# wqm.net
KiCad netlist of a schematic drawn in EAGLE
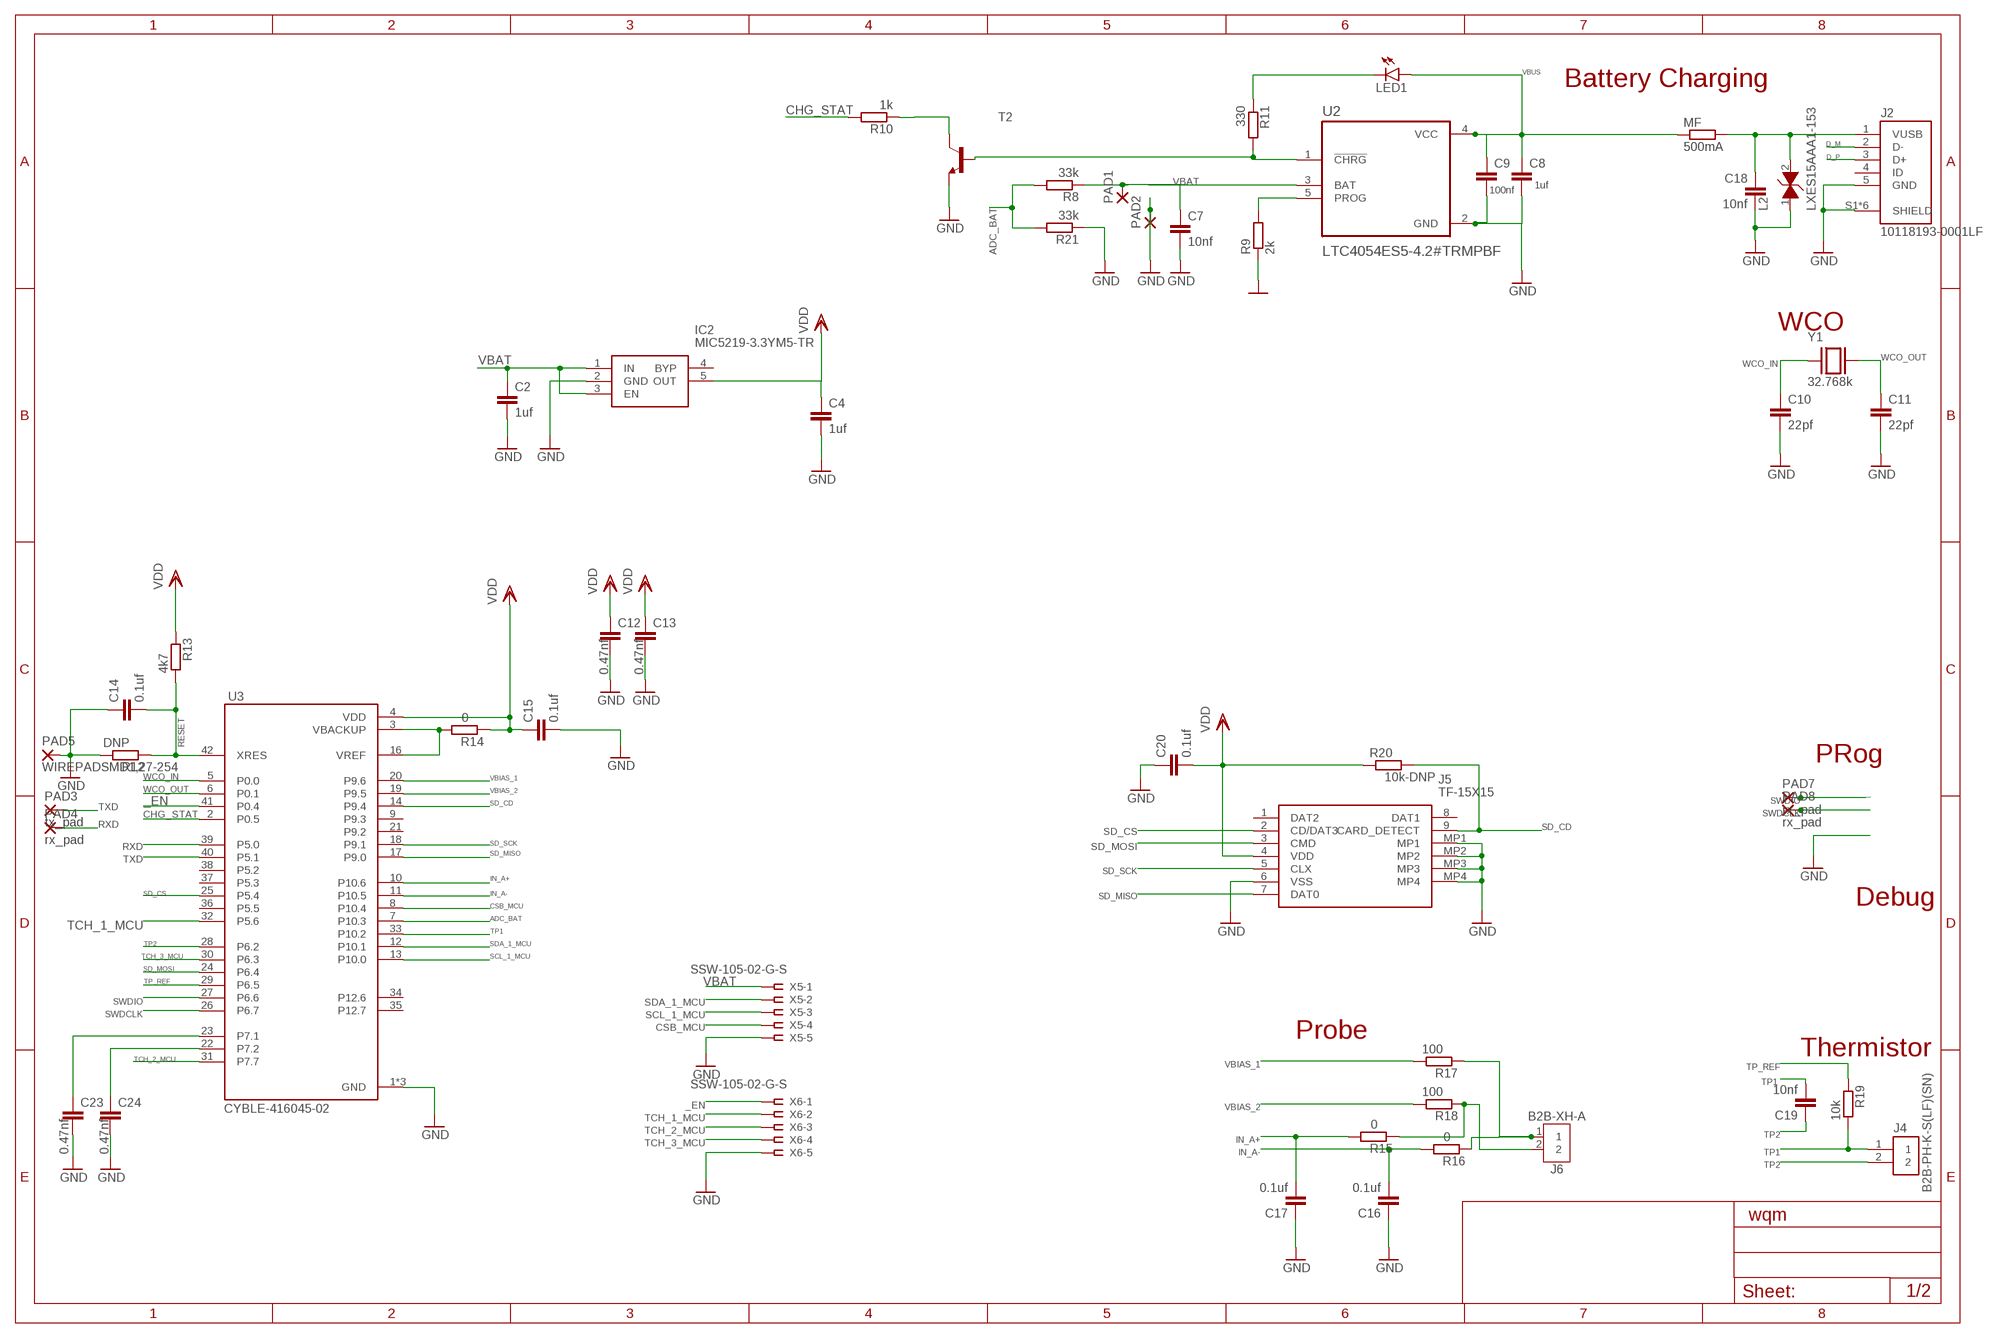
[diagram p0: schematic, sheet 1]
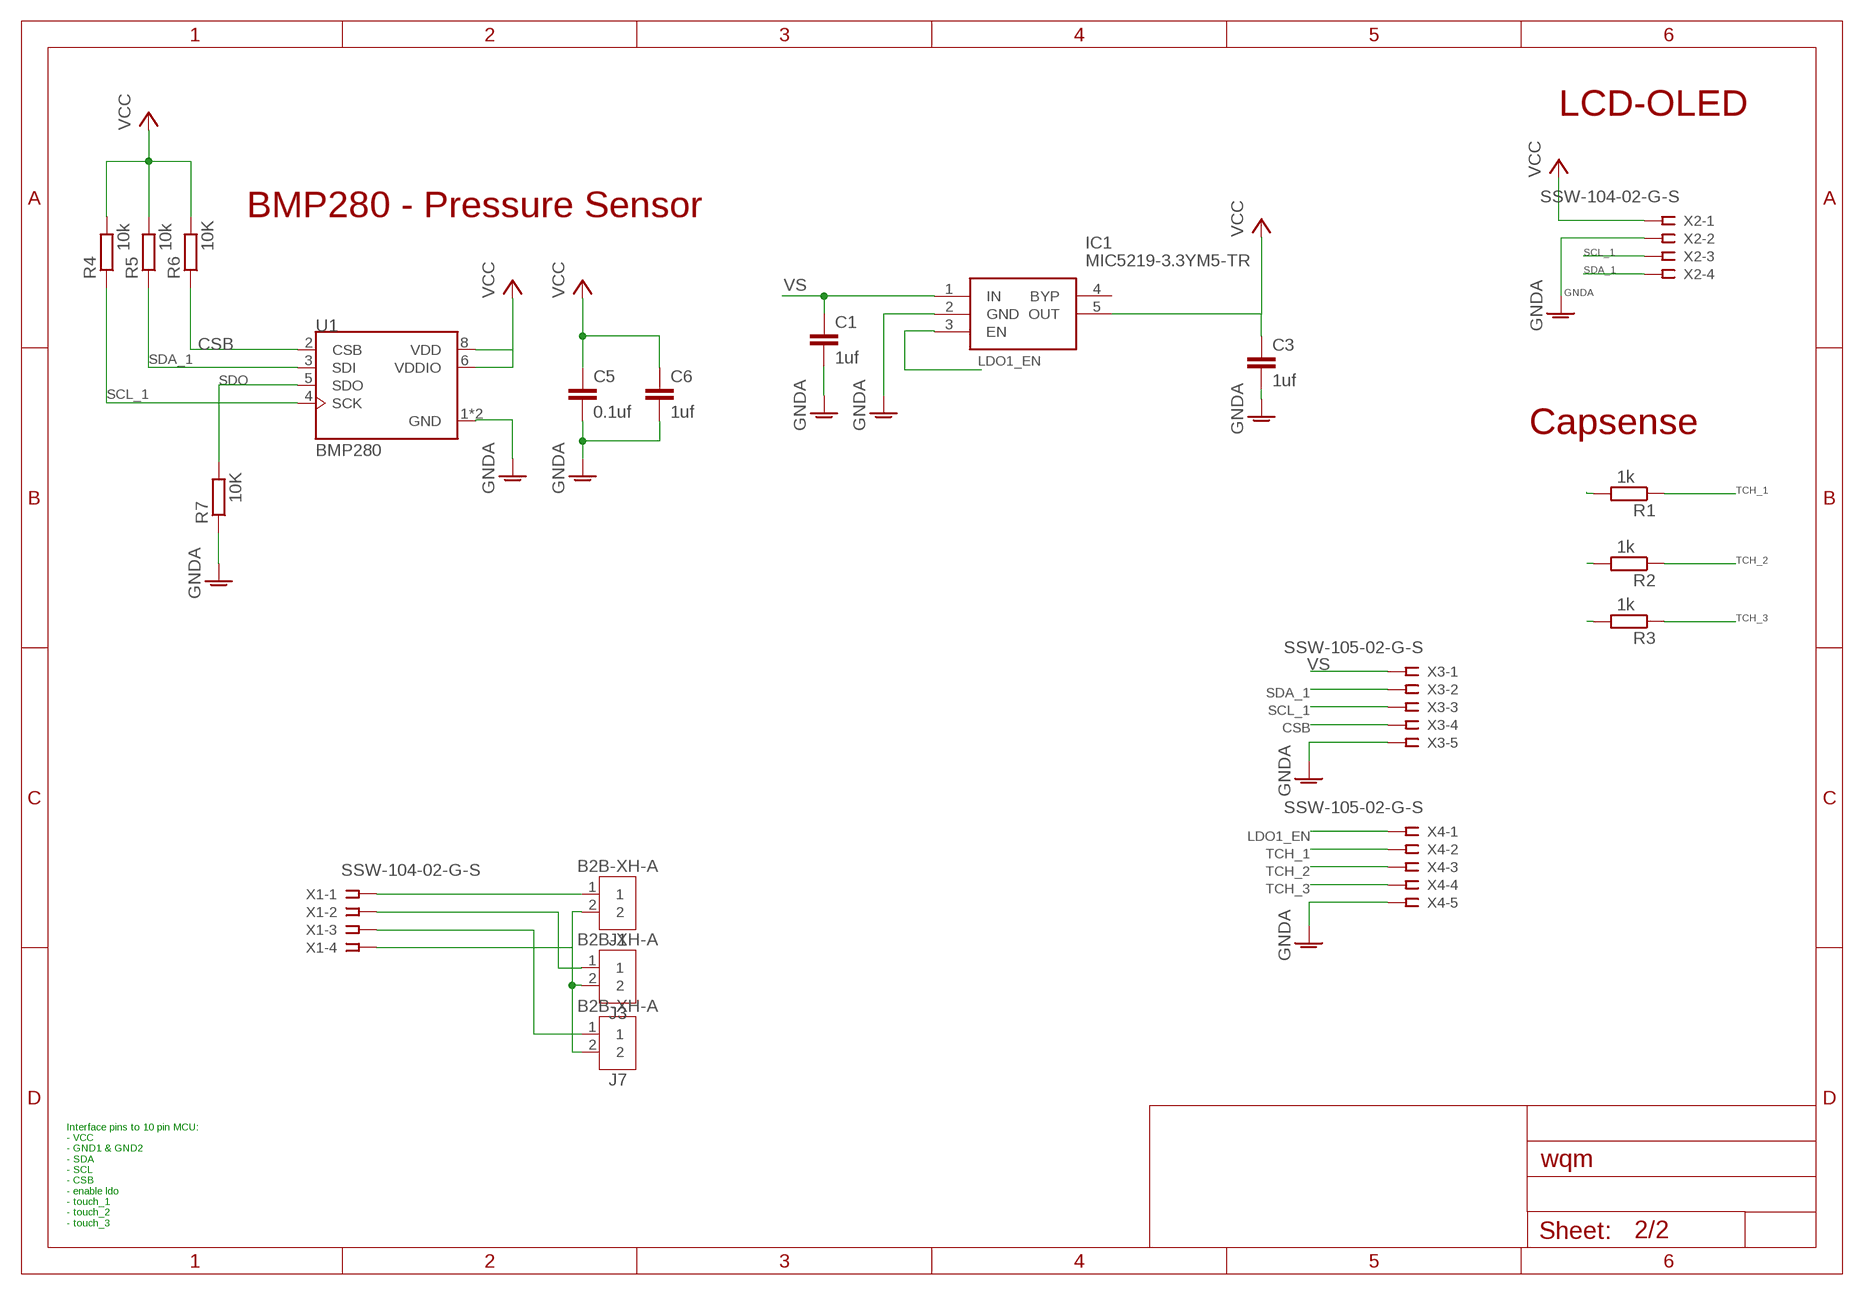
[diagram p1: schematic, sheet 2]

(export (version "E")
  (design (tool "Eeschema 10.0.6"))
  (components
    (comp (ref "C2")
      (value "1uf")
      (footprint "eagle-import:C0603K")
      (libsource (lib "eagle-import") (part "C-EUC0603K"))
    )
    (comp (ref "C4")
      (value "1uf")
      (footprint "eagle-import:C0603K")
      (libsource (lib "eagle-import") (part "C-EUC0603K"))
    )
    (comp (ref "C7")
      (value "10nf")
      (footprint "eagle-import:C0603K")
      (libsource (lib "eagle-import") (part "C-EUC0603K"))
    )
    (comp (ref "C8")
      (value "1uf")
      (footprint "eagle-import:C0603K")
      (libsource (lib "eagle-import") (part "C-EUC0603K"))
    )
    (comp (ref "C9")
      (value "100nf")
      (footprint "eagle-import:C0603K")
      (libsource (lib "eagle-import") (part "C-EUC0603K"))
    )
    (comp (ref "C10")
      (value "22pf")
      (footprint "eagle-import:C0402K")
      (libsource (lib "eagle-import") (part "C-EUC0402K"))
    )
    (comp (ref "C11")
      (value "22pf")
      (footprint "eagle-import:C0402K")
      (libsource (lib "eagle-import") (part "C-EUC0402K"))
    )
    (comp (ref "C12")
      (value "0.47nf")
      (footprint "eagle-import:C0402K")
      (libsource (lib "eagle-import") (part "C-EUC0402K"))
    )
    (comp (ref "C13")
      (value "0.47nf")
      (footprint "eagle-import:C0402K")
      (libsource (lib "eagle-import") (part "C-EUC0402K"))
    )
    (comp (ref "C14")
      (value "0.1uf")
      (footprint "eagle-import:C0402K")
      (libsource (lib "eagle-import") (part "C-EUC0402K"))
    )
    (comp (ref "C15")
      (value "0.1uf")
      (footprint "eagle-import:C0603K")
      (libsource (lib "eagle-import") (part "C-EUC0603K"))
    )
    (comp (ref "C16")
      (value "0.1uf")
      (footprint "eagle-import:C0603K")
      (libsource (lib "eagle-import") (part "C-EUC0603K"))
    )
    (comp (ref "C17")
      (value "0.1uf")
      (footprint "eagle-import:C0603K")
      (libsource (lib "eagle-import") (part "C-EUC0603K"))
    )
    (comp (ref "C18")
      (value "10nf")
      (footprint "eagle-import:C0402K")
      (libsource (lib "eagle-import") (part "C-EUC0402K"))
    )
    (comp (ref "C19")
      (value "10nf")
      (footprint "eagle-import:C0402K")
      (libsource (lib "eagle-import") (part "C-EUC0402K"))
    )
    (comp (ref "C20")
      (value "0.1uf")
      (footprint "eagle-import:C0603K")
      (libsource (lib "eagle-import") (part "C-EUC0603K"))
    )
    (comp (ref "C23")
      (value "0.47nf")
      (footprint "eagle-import:C0402K")
      (libsource (lib "eagle-import") (part "C-EUC0402K"))
    )
    (comp (ref "C24")
      (value "0.47nf")
      (footprint "eagle-import:C0402K")
      (libsource (lib "eagle-import") (part "C-EUC0402K"))
    )
    (comp (ref "IC2")
      (value "MIC5219-3.3YM5-TR")
      (footprint "eagle-import:SOT95P280X145-5N")
      (fields (field (name "MOUSER_PART_NUMBER") "998-MIC5219-3.3YM5TR"))
      (libsource (lib "eagle-import") (part "MIC5219-3.3YM5-TR"))
    )
    (comp (ref "J2")
      (value "10118193-0001LF")
      (footprint "eagle-import:AMPHENOL_10118193-0001LF")
      (fields (field (name "MF") "Amphenol"))
      (libsource (lib "eagle-import") (part "10118193-0001LF"))
    )
    (comp (ref "J4")
      (value "B2B-PH-K-S(LF)(SN)")
      (footprint "eagle-import:JST_B2B-PH-K-S(LF)(SN)")
      (fields (field (name "MF") "JST Sales"))
      (libsource (lib "eagle-import") (part "B2B-PH-K-S(LF)(SN)"))
    )
    (comp (ref "J5")
      (value "TF-15X15")
      (footprint "eagle-import:TF15X15")
      (libsource (lib "eagle-import") (part "TF-15X15"))
    )
    (comp (ref "J6")
      (value "B2B-XH-A")
      (footprint "eagle-import:B2B-XH-A")
      (fields (field (name "MF") "JST Sales"))
      (libsource (lib "eagle-import") (part "B2B-XH-A"))
    )
    (comp (ref "L2")
      (value "LXES15AAA1-153")
      (footprint "eagle-import:INDC1005X45")
      (fields (field (name "MF") "Murata"))
      (libsource (lib "eagle-import") (part "LXES15AAA1-153"))
    )
    (comp (ref "LED1")
      (value "LEDSML0603")
      (footprint "eagle-import:SML0603")
      (libsource (lib "eagle-import") (part "LEDSML0603"))
    )
    (comp (ref "MF")
      (value "500mA")
      (footprint "eagle-import:R0805")
      (libsource (lib "eagle-import") (part "R-EU_R0805"))
    )
    (comp (ref "PAD1")
      (value "SMD2")
      (footprint "eagle-import:SMD1,27-2,54")
      (libsource (lib "eagle-import") (part "SMD2"))
    )
    (comp (ref "PAD2")
      (value "SMD2")
      (footprint "eagle-import:SMD1,27-2,54")
      (libsource (lib "eagle-import") (part "SMD2"))
    )
    (comp (ref "PAD3")
      (value "tx_pad")
      (footprint "eagle-import:SMD1,27-2,54")
      (libsource (lib "eagle-import") (part "WIREPADSMD1,27-254"))
    )
    (comp (ref "PAD4")
      (value "rx_pad")
      (footprint "eagle-import:SMD1,27-2,54")
      (libsource (lib "eagle-import") (part "WIREPADSMD1,27-254"))
    )
    (comp (ref "PAD5")
      (value "WIREPADSMD1,27-254")
      (footprint "eagle-import:SMD1,27-2,54")
      (libsource (lib "eagle-import") (part "WIREPADSMD1,27-254"))
    )
    (comp (ref "PAD7")
      (value "rx_pad")
      (footprint "eagle-import:SMD1,27-2,54")
      (libsource (lib "eagle-import") (part "WIREPADSMD1,27-254"))
    )
    (comp (ref "PAD8")
      (value "rx_pad")
      (footprint "eagle-import:SMD1,27-2,54")
      (libsource (lib "eagle-import") (part "WIREPADSMD1,27-254"))
    )
    (comp (ref "R8")
      (value "33k")
      (footprint "eagle-import:R0603")
      (libsource (lib "eagle-import") (part "R-EU_R0603"))
    )
    (comp (ref "R9")
      (value "2k")
      (footprint "eagle-import:R0603")
      (libsource (lib "eagle-import") (part "R-EU_R0603"))
    )
    (comp (ref "R10")
      (value "1k")
      (footprint "eagle-import:R0603")
      (libsource (lib "eagle-import") (part "R-EU_R0603"))
    )
    (comp (ref "R11")
      (value "330")
      (footprint "eagle-import:R0603")
      (libsource (lib "eagle-import") (part "R-EU_R0603"))
    )
    (comp (ref "R12")
      (value "DNP")
      (footprint "eagle-import:R0603")
      (libsource (lib "eagle-import") (part "R-EU_R0603"))
    )
    (comp (ref "R13")
      (value "4k7")
      (footprint "eagle-import:R0603")
      (libsource (lib "eagle-import") (part "R-EU_R0603"))
    )
    (comp (ref "R14")
      (value "0")
      (footprint "eagle-import:R0603")
      (libsource (lib "eagle-import") (part "R-EU_R0603"))
    )
    (comp (ref "R15")
      (value "0")
      (footprint "eagle-import:R0603")
      (libsource (lib "eagle-import") (part "R-EU_R0603"))
    )
    (comp (ref "R16")
      (value "0")
      (footprint "eagle-import:R0603")
      (libsource (lib "eagle-import") (part "R-EU_R0603"))
    )
    (comp (ref "R17")
      (value "100")
      (footprint "eagle-import:R0603")
      (libsource (lib "eagle-import") (part "R-EU_R0603"))
    )
    (comp (ref "R18")
      (value "100")
      (footprint "eagle-import:R0603")
      (libsource (lib "eagle-import") (part "R-EU_R0603"))
    )
    (comp (ref "R19")
      (value "10k")
      (footprint "eagle-import:R0603")
      (libsource (lib "eagle-import") (part "R-EU_R0603"))
    )
    (comp (ref "R20")
      (value "10k-DNP")
      (footprint "eagle-import:R0603")
      (libsource (lib "eagle-import") (part "R-EU_R0603"))
    )
    (comp (ref "R21")
      (value "33k")
      (footprint "eagle-import:R0603")
      (libsource (lib "eagle-import") (part "R-EU_R0603"))
    )
    (comp (ref "T2")
      (value "MMBT4401LT1-NPN-SOT23-BEC")
      (footprint "eagle-import:SOT23-BEC")
      (libsource (lib "eagle-import") (part "-NPN-SOT23-BECMMBT4401LT1"))
    )
    (comp (ref "U2")
      (value "LTC4054ES5-4.2#TRMPBF")
      (footprint "eagle-import:SOT95P280X100-5N")
      (fields (field (name "MF") "Analog Devices"))
      (libsource (lib "eagle-import") (part "LTC4054ES5-4.2#TRMPBF"))
    )
    (comp (ref "U3")
      (value "CYBLE-416045-02")
      (footprint "eagle-import:XCVR_CYBLE-416045-02")
      (fields (field (name "MF") "Cypress Semiconductor"))
      (libsource (lib "eagle-import") (part "CYBLE-416045-02"))
    )
    (comp (ref "X5")
      (value "SSW-105-02-G-S")
      (footprint "eagle-import:SSW-105-02-G-S")
      (fields (field (name "MF") "Samtec Inc."))
      (libsource (lib "eagle-import") (part "SSW-105-02-G-S"))
    )
    (comp (ref "X6")
      (value "SSW-105-02-G-S")
      (footprint "eagle-import:SSW-105-02-G-S")
      (fields (field (name "MF") "Samtec Inc."))
      (libsource (lib "eagle-import") (part "SSW-105-02-G-S"))
    )
    (comp (ref "Y1")
      (value "32.768k")
      (footprint "eagle-import:XTAL_MS3V-T1R")
      (fields (field (name "MF") "Micro Crystal") (field (name "MP") "MS3V-T1R"))
      (libsource (lib "eagle-import") (part "MS3V-T1R"))
    )
    (comp (ref "C1")
      (value "1uf")
      (footprint "eagle-import:C0603K")
      (libsource (lib "eagle-import") (part "C-EUC0603K"))
    )
    (comp (ref "C3")
      (value "1uf")
      (footprint "eagle-import:C0603K")
      (libsource (lib "eagle-import") (part "C-EUC0603K"))
    )
    (comp (ref "C5")
      (value "0.1uf")
      (footprint "eagle-import:C0603K")
      (libsource (lib "eagle-import") (part "C-EUC0603K"))
    )
    (comp (ref "C6")
      (value "1uf")
      (footprint "eagle-import:C0603K")
      (libsource (lib "eagle-import") (part "C-EUC0603K"))
    )
    (comp (ref "IC1")
      (value "MIC5219-3.3YM5-TR")
      (footprint "eagle-import:SOT95P280X145-5N")
      (fields (field (name "MOUSER_PART_NUMBER") "998-MIC5219-3.3YM5TR"))
      (libsource (lib "eagle-import") (part "MIC5219-3.3YM5-TR"))
    )
    (comp (ref "J1")
      (value "B2B-XH-A")
      (footprint "eagle-import:B2B-XH-A")
      (fields (field (name "MF") "JST Sales"))
      (libsource (lib "eagle-import") (part "B2B-XH-A"))
    )
    (comp (ref "J3")
      (value "B2B-XH-A")
      (footprint "eagle-import:B2B-XH-A")
      (fields (field (name "MF") "JST Sales"))
      (libsource (lib "eagle-import") (part "B2B-XH-A"))
    )
    (comp (ref "J7")
      (value "B2B-XH-A")
      (footprint "eagle-import:B2B-XH-A")
      (fields (field (name "MF") "JST Sales"))
      (libsource (lib "eagle-import") (part "B2B-XH-A"))
    )
    (comp (ref "R1")
      (value "1k")
      (footprint "eagle-import:R0603")
      (libsource (lib "eagle-import") (part "R-EU_R0603"))
    )
    (comp (ref "R2")
      (value "1k")
      (footprint "eagle-import:R0603")
      (libsource (lib "eagle-import") (part "R-EU_R0603"))
    )
    (comp (ref "R3")
      (value "1k")
      (footprint "eagle-import:R0603")
      (libsource (lib "eagle-import") (part "R-EU_R0603"))
    )
    (comp (ref "R4")
      (value "10k")
      (footprint "eagle-import:R0603")
      (libsource (lib "eagle-import") (part "R-EU_R0603"))
    )
    (comp (ref "R5")
      (value "10k")
      (footprint "eagle-import:R0603")
      (libsource (lib "eagle-import") (part "R-EU_R0603"))
    )
    (comp (ref "R6")
      (value "10K")
      (footprint "eagle-import:R0603")
      (libsource (lib "eagle-import") (part "R-EU_R0603"))
    )
    (comp (ref "R7")
      (value "10K")
      (footprint "eagle-import:R0603")
      (libsource (lib "eagle-import") (part "R-EU_R0603"))
    )
    (comp (ref "U1")
      (value "BMP280")
      (footprint "eagle-import:XDCR_BMP280")
      (fields (field (name "MF") "Bosch"))
      (libsource (lib "eagle-import") (part "BMP280"))
    )
    (comp (ref "X1")
      (value "SSW-104-02-G-S")
      (footprint "eagle-import:SSW-104-02-G-S")
      (fields (field (name "MF") "Samtec Inc."))
      (libsource (lib "eagle-import") (part "SSW-104-02-G-S"))
    )
    (comp (ref "X2")
      (value "SSW-104-02-G-S")
      (footprint "eagle-import:SSW-104-02-G-S")
      (fields (field (name "MF") "Samtec Inc."))
      (libsource (lib "eagle-import") (part "SSW-104-02-G-S"))
    )
    (comp (ref "X3")
      (value "SSW-105-02-G-S")
      (footprint "eagle-import:SSW-105-02-G-S")
      (fields (field (name "MF") "Samtec Inc."))
      (libsource (lib "eagle-import") (part "SSW-105-02-G-S"))
    )
    (comp (ref "X4")
      (value "SSW-105-02-G-S")
      (footprint "eagle-import:SSW-105-02-G-S")
      (fields (field (name "MF") "Samtec Inc."))
      (libsource (lib "eagle-import") (part "SSW-105-02-G-S"))
    )
  )
  (nets
    (net (code "1") (name "ADC_BAT") (class "Default")
      (node (ref "R21") (pin "2") (pinfunction "2_2") (pintype "passive"))
      (node (ref "R8") (pin "2") (pinfunction "2_2") (pintype "passive"))
      (node (ref "U3") (pin "7") (pinfunction "P10.3_7") (pintype "bidirectional"))
    )
    (net (code "2") (name "CHG_STAT") (class "Default")
      (node (ref "R10") (pin "2") (pinfunction "2_2") (pintype "passive"))
      (node (ref "U3") (pin "2") (pinfunction "P0.5_2") (pintype "bidirectional"))
    )
    (net (code "3") (name "CSB") (class "Default")
      (node (ref "R6") (pin "1") (pinfunction "1_1") (pintype "passive"))
      (node (ref "U1") (pin "2") (pinfunction "CSB_2") (pintype "input"))
      (node (ref "X3") (pin "4") (pinfunction "1_4") (pintype "passive"))
    )
    (net (code "4") (name "CSB_MCU") (class "Default")
      (node (ref "U3") (pin "8") (pinfunction "P10.4_8") (pintype "bidirectional"))
      (node (ref "X5") (pin "4") (pinfunction "1_4") (pintype "passive"))
    )
    (net (code "5") (name "D_M") (class "Default")
      (node (ref "J2") (pin "2") (pinfunction "D-_2") (pintype "passive"))
    )
    (net (code "6") (name "D_P") (class "Default")
      (node (ref "J2") (pin "3") (pinfunction "D+_3") (pintype "passive"))
    )
    (net (code "7") (name "GND") (class "Default")
      (node (ref "C10") (pin "2") (pinfunction "2_2") (pintype "passive"))
      (node (ref "C11") (pin "2") (pinfunction "2_2") (pintype "passive"))
      (node (ref "C12") (pin "2") (pinfunction "2_2") (pintype "passive"))
      (node (ref "C13") (pin "2") (pinfunction "2_2") (pintype "passive"))
      (node (ref "C14") (pin "1") (pinfunction "1_1") (pintype "passive"))
      (node (ref "C15") (pin "2") (pinfunction "2_2") (pintype "passive"))
      (node (ref "C16") (pin "1") (pinfunction "1_1") (pintype "passive"))
      (node (ref "C17") (pin "1") (pinfunction "1_1") (pintype "passive"))
      (node (ref "C18") (pin "2") (pinfunction "2_2") (pintype "passive"))
      (node (ref "C2") (pin "2") (pinfunction "2_2") (pintype "passive"))
      (node (ref "C20") (pin "1") (pinfunction "1_1") (pintype "passive"))
      (node (ref "C23") (pin "2") (pinfunction "2_2") (pintype "passive"))
      (node (ref "C24") (pin "2") (pinfunction "2_2") (pintype "passive"))
      (node (ref "C4") (pin "2") (pinfunction "2_2") (pintype "passive"))
      (node (ref "C7") (pin "2") (pinfunction "2_2") (pintype "passive"))
      (node (ref "C8") (pin "2") (pinfunction "2_2") (pintype "passive"))
      (node (ref "C9") (pin "2") (pinfunction "2_2") (pintype "passive"))
      (node (ref "IC2") (pin "2") (pinfunction "GND_2") (pintype "bidirectional"))
      (node (ref "J2") (pin "5") (pinfunction "GND_5") (pintype "passive"))
      (node (ref "J2") (pin "S1") (pinfunction "SHIELD_S1") (pintype "passive"))
      (node (ref "J2") (pin "S2") (pinfunction "SHIELD_S2") (pintype "passive"))
      (node (ref "J2") (pin "S3") (pinfunction "SHIELD_S3") (pintype "passive"))
      (node (ref "J2") (pin "S4") (pinfunction "SHIELD_S4") (pintype "passive"))
      (node (ref "J2") (pin "S5") (pinfunction "SHIELD_S5") (pintype "passive"))
      (node (ref "J2") (pin "S6") (pinfunction "SHIELD_S6") (pintype "passive"))
      (node (ref "J5") (pin "6") (pinfunction "VSS_6") (pintype "bidirectional"))
      (node (ref "J5") (pin "MP1") (pinfunction "MP1_MP1") (pintype "bidirectional"))
      (node (ref "J5") (pin "MP2") (pinfunction "MP2_MP2") (pintype "bidirectional"))
      (node (ref "J5") (pin "MP3") (pinfunction "MP3_MP3") (pintype "bidirectional"))
      (node (ref "J5") (pin "MP4") (pinfunction "MP4_MP4") (pintype "bidirectional"))
      (node (ref "L2") (pin "1") (pinfunction "1_1") (pintype "passive"))
      (node (ref "PAD2") (pin "1") (pinfunction "P_1") (pintype "passive"))
      (node (ref "PAD5") (pin "1") (pinfunction "P_1") (pintype "passive"))
      (node (ref "R12") (pin "2") (pinfunction "2_2") (pintype "passive"))
      (node (ref "R21") (pin "1") (pinfunction "1_1") (pintype "passive"))
      (node (ref "R9") (pin "1") (pinfunction "1_1") (pintype "passive"))
      (node (ref "T2") (pin "E") (pinfunction "E_E") (pintype "passive"))
      (node (ref "U2") (pin "2") (pinfunction "GND_2") (pintype "power_in"))
      (node (ref "U3") (pin "1") (pinfunction "GND_1") (pintype "power_in"))
      (node (ref "U3") (pin "15") (pinfunction "GND_15") (pintype "power_in"))
      (node (ref "U3") (pin "43") (pinfunction "GND_43") (pintype "power_in"))
      (node (ref "X5") (pin "5") (pinfunction "1_5") (pintype "passive"))
      (node (ref "X6") (pin "5") (pinfunction "1_5") (pintype "passive"))
    )
    (net (code "8") (name "GNDA") (class "Default")
      (node (ref "C1") (pin "2") (pinfunction "2_2") (pintype "passive"))
      (node (ref "C3") (pin "2") (pinfunction "2_2") (pintype "passive"))
      (node (ref "C5") (pin "2") (pinfunction "2_2") (pintype "passive"))
      (node (ref "C6") (pin "2") (pinfunction "2_2") (pintype "passive"))
      (node (ref "IC1") (pin "2") (pinfunction "GND_2") (pintype "bidirectional"))
      (node (ref "R7") (pin "1") (pinfunction "1_1") (pintype "passive"))
      (node (ref "U1") (pin "1") (pinfunction "GND_1") (pintype "power_in"))
      (node (ref "U1") (pin "7") (pinfunction "GND_7") (pintype "power_in"))
      (node (ref "X2") (pin "2") (pinfunction "1_2") (pintype "passive"))
      (node (ref "X3") (pin "5") (pinfunction "1_5") (pintype "passive"))
      (node (ref "X4") (pin "5") (pinfunction "1_5") (pintype "passive"))
    )
    (net (code "9") (name "IN_A+") (class "Default")
      (node (ref "C17") (pin "2") (pinfunction "2_2") (pintype "passive"))
      (node (ref "R15") (pin "2") (pinfunction "2_2") (pintype "passive"))
      (node (ref "U3") (pin "10") (pinfunction "P10.6_10") (pintype "bidirectional"))
    )
    (net (code "10") (name "IN_A-") (class "Default")
      (node (ref "C16") (pin "2") (pinfunction "2_2") (pintype "passive"))
      (node (ref "R16") (pin "2") (pinfunction "2_2") (pintype "passive"))
      (node (ref "U3") (pin "11") (pinfunction "P10.5_11") (pintype "bidirectional"))
    )
    (net (code "11") (name "LDO1_EN") (class "Default")
      (node (ref "IC1") (pin "3") (pinfunction "EN_3") (pintype "bidirectional"))
      (node (ref "X4") (pin "1") (pinfunction "1_1") (pintype "passive"))
    )
    (net (code "12") (name "Net-(J1-Pad1)") (class "Default")
      (node (ref "J1") (pin "1") (pinfunction "1_1") (pintype "bidirectional"))
      (node (ref "X1") (pin "1") (pinfunction "1_1") (pintype "passive"))
    )
    (net (code "13") (name "Net-(J2-VUSB)") (class "Default")
      (node (ref "C18") (pin "1") (pinfunction "1_1") (pintype "passive"))
      (node (ref "J2") (pin "1") (pinfunction "VUSB_1") (pintype "passive"))
      (node (ref "L2") (pin "2") (pinfunction "2_2") (pintype "passive"))
      (node (ref "MF") (pin "2") (pinfunction "2_2") (pintype "passive"))
    )
    (net (code "14") (name "Net-(J6-Pad1)") (class "Default")
      (node (ref "J6") (pin "1") (pinfunction "1_1") (pintype "bidirectional"))
      (node (ref "R16") (pin "1") (pinfunction "1_1") (pintype "passive"))
      (node (ref "R17") (pin "1") (pinfunction "1_1") (pintype "passive"))
    )
    (net (code "15") (name "Net-(J6-Pad2)") (class "Default")
      (node (ref "J6") (pin "2") (pinfunction "2_2") (pintype "bidirectional"))
      (node (ref "R15") (pin "1") (pinfunction "1_1") (pintype "passive"))
      (node (ref "R18") (pin "1") (pinfunction "1_1") (pintype "passive"))
    )
    (net (code "16") (name "Net-(LED1-PadC)") (class "Default")
      (node (ref "LED1") (pin "C") (pinfunction "C_C") (pintype "passive"))
      (node (ref "R11") (pin "1") (pinfunction "1_1") (pintype "passive"))
    )
    (net (code "17") (name "Net-(R10-Pad1)") (class "Default")
      (node (ref "R10") (pin "1") (pinfunction "1_1") (pintype "passive"))
      (node (ref "T2") (pin "C") (pinfunction "C_C") (pintype "passive"))
    )
    (net (code "18") (name "Net-(U2-PROG)") (class "Default")
      (node (ref "R9") (pin "2") (pinfunction "2_2") (pintype "passive"))
      (node (ref "U2") (pin "5") (pinfunction "PROG_5") (pintype "bidirectional"))
    )
    (net (code "19") (name "Net-(U2-~{CHRG})") (class "Default")
      (node (ref "R11") (pin "2") (pinfunction "2_2") (pintype "passive"))
      (node (ref "T2") (pin "B") (pinfunction "B_B") (pintype "passive"))
      (node (ref "U2") (pin "1") (pinfunction "~{CHRG}_1") (pintype "input"))
    )
    (net (code "20") (name "Net-(U3-P7.1)") (class "Default")
      (node (ref "C23") (pin "1") (pinfunction "1_1") (pintype "passive"))
      (node (ref "U3") (pin "23") (pinfunction "P7.1_23") (pintype "bidirectional"))
    )
    (net (code "21") (name "Net-(U3-P7.2)") (class "Default")
      (node (ref "C24") (pin "1") (pinfunction "1_1") (pintype "passive"))
      (node (ref "U3") (pin "22") (pinfunction "P7.2_22") (pintype "bidirectional"))
    )
    (net (code "22") (name "Net-(U3-VBACKUP)") (class "Default")
      (node (ref "R14") (pin "2") (pinfunction "2_2") (pintype "passive"))
      (node (ref "U3") (pin "16") (pinfunction "VREF_16") (pintype "bidirectional"))
      (node (ref "U3") (pin "3") (pinfunction "VBACKUP_3") (pintype "power_in"))
    )
    (net (code "23") (name "Net-(X1B-1)") (class "Default")
      (node (ref "J3") (pin "1") (pinfunction "1_1") (pintype "bidirectional"))
      (node (ref "X1") (pin "2") (pinfunction "1_2") (pintype "passive"))
    )
    (net (code "24") (name "Net-(X1C-1)") (class "Default")
      (node (ref "J7") (pin "1") (pinfunction "1_1") (pintype "bidirectional"))
      (node (ref "X1") (pin "3") (pinfunction "1_3") (pintype "passive"))
    )
    (net (code "25") (name "Net-(X1D-1)") (class "Default")
      (node (ref "J1") (pin "2") (pinfunction "2_2") (pintype "bidirectional"))
      (node (ref "J3") (pin "2") (pinfunction "2_2") (pintype "bidirectional"))
      (node (ref "J7") (pin "2") (pinfunction "2_2") (pintype "bidirectional"))
      (node (ref "X1") (pin "4") (pinfunction "1_4") (pintype "passive"))
    )
    (net (code "26") (name "RESET") (class "Default")
      (node (ref "C14") (pin "2") (pinfunction "2_2") (pintype "passive"))
      (node (ref "R12") (pin "1") (pinfunction "1_1") (pintype "passive"))
      (node (ref "R13") (pin "2") (pinfunction "2_2") (pintype "passive"))
      (node (ref "U3") (pin "42") (pinfunction "XRES_42") (pintype "input"))
    )
    (net (code "27") (name "RXD") (class "Default")
      (node (ref "PAD4") (pin "1") (pinfunction "P_1") (pintype "passive"))
      (node (ref "U3") (pin "39") (pinfunction "P5.0_39") (pintype "bidirectional"))
    )
    (net (code "28") (name "SCL_1") (class "Default")
      (node (ref "R4") (pin "1") (pinfunction "1_1") (pintype "passive"))
      (node (ref "U1") (pin "4") (pinfunction "SCK_4") (pintype "input"))
      (node (ref "X2") (pin "3") (pinfunction "1_3") (pintype "passive"))
      (node (ref "X3") (pin "3") (pinfunction "1_3") (pintype "passive"))
    )
    (net (code "29") (name "SCL_1_MCU") (class "Default")
      (node (ref "U3") (pin "13") (pinfunction "P10.0_13") (pintype "bidirectional"))
      (node (ref "X5") (pin "3") (pinfunction "1_3") (pintype "passive"))
    )
    (net (code "30") (name "SDA_1") (class "Default")
      (node (ref "R5") (pin "1") (pinfunction "1_1") (pintype "passive"))
      (node (ref "U1") (pin "3") (pinfunction "SDI_3") (pintype "bidirectional"))
      (node (ref "X2") (pin "4") (pinfunction "1_4") (pintype "passive"))
      (node (ref "X3") (pin "2") (pinfunction "1_2") (pintype "passive"))
    )
    (net (code "31") (name "SDA_1_MCU") (class "Default")
      (node (ref "U3") (pin "12") (pinfunction "P10.1_12") (pintype "bidirectional"))
      (node (ref "X5") (pin "2") (pinfunction "1_2") (pintype "passive"))
    )
    (net (code "32") (name "SDO") (class "Default")
      (node (ref "R7") (pin "2") (pinfunction "2_2") (pintype "passive"))
      (node (ref "U1") (pin "5") (pinfunction "SDO_5") (pintype "bidirectional"))
    )
    (net (code "33") (name "SD_CD") (class "Default")
      (node (ref "J5") (pin "9") (pinfunction "CARD_DETECT_9") (pintype "bidirectional"))
      (node (ref "R20") (pin "2") (pinfunction "2_2") (pintype "passive"))
      (node (ref "U3") (pin "14") (pinfunction "P9.4_14") (pintype "bidirectional"))
    )
    (net (code "34") (name "SD_CS") (class "Default")
      (node (ref "J5") (pin "2") (pinfunction "CD/DAT3_2") (pintype "bidirectional"))
      (node (ref "U3") (pin "25") (pinfunction "P5.4_25") (pintype "bidirectional"))
    )
    (net (code "35") (name "SD_MISO") (class "Default")
      (node (ref "J5") (pin "7") (pinfunction "DAT0_7") (pintype "bidirectional"))
      (node (ref "U3") (pin "17") (pinfunction "P9.0_17") (pintype "bidirectional"))
    )
    (net (code "36") (name "SD_MOSI") (class "Default")
      (node (ref "J5") (pin "3") (pinfunction "CMD_3") (pintype "bidirectional"))
      (node (ref "U3") (pin "24") (pinfunction "P6.4_24") (pintype "bidirectional"))
    )
    (net (code "37") (name "SD_SCK") (class "Default")
      (node (ref "J5") (pin "5") (pinfunction "CLX_5") (pintype "bidirectional"))
      (node (ref "U3") (pin "18") (pinfunction "P9.1_18") (pintype "bidirectional"))
    )
    (net (code "38") (name "SWDCLK") (class "Default")
      (node (ref "PAD8") (pin "1") (pinfunction "P_1") (pintype "passive"))
      (node (ref "U3") (pin "26") (pinfunction "P6.7_26") (pintype "bidirectional"))
    )
    (net (code "39") (name "SWDIO") (class "Default")
      (node (ref "PAD7") (pin "1") (pinfunction "P_1") (pintype "passive"))
      (node (ref "U3") (pin "27") (pinfunction "P6.6_27") (pintype "bidirectional"))
    )
    (net (code "40") (name "TCH_1") (class "Default")
      (node (ref "R1") (pin "1") (pinfunction "1_1") (pintype "passive"))
      (node (ref "X4") (pin "2") (pinfunction "1_2") (pintype "passive"))
    )
    (net (code "41") (name "TCH_1_MCU") (class "Default")
      (node (ref "U3") (pin "32") (pinfunction "P5.6_32") (pintype "bidirectional"))
      (node (ref "X6") (pin "2") (pinfunction "1_2") (pintype "passive"))
    )
    (net (code "42") (name "TCH_2") (class "Default")
      (node (ref "R2") (pin "1") (pinfunction "1_1") (pintype "passive"))
      (node (ref "X4") (pin "3") (pinfunction "1_3") (pintype "passive"))
    )
    (net (code "43") (name "TCH_2_MCU") (class "Default")
      (node (ref "U3") (pin "31") (pinfunction "P7.7_31") (pintype "bidirectional"))
      (node (ref "X6") (pin "3") (pinfunction "1_3") (pintype "passive"))
    )
    (net (code "44") (name "TCH_3") (class "Default")
      (node (ref "R3") (pin "1") (pinfunction "1_1") (pintype "passive"))
      (node (ref "X4") (pin "4") (pinfunction "1_4") (pintype "passive"))
    )
    (net (code "45") (name "TCH_3_MCU") (class "Default")
      (node (ref "U3") (pin "30") (pinfunction "P6.3_30") (pintype "bidirectional"))
      (node (ref "X6") (pin "4") (pinfunction "1_4") (pintype "passive"))
    )
    (net (code "46") (name "TP1") (class "Default")
      (node (ref "C19") (pin "2") (pinfunction "2_2") (pintype "passive"))
      (node (ref "J4") (pin "1") (pinfunction "1_1") (pintype "passive"))
      (node (ref "R19") (pin "2") (pinfunction "2_2") (pintype "passive"))
      (node (ref "U3") (pin "33") (pinfunction "P10.2_33") (pintype "bidirectional"))
    )
    (net (code "47") (name "TP2") (class "Default")
      (node (ref "C19") (pin "1") (pinfunction "1_1") (pintype "passive"))
      (node (ref "J4") (pin "2") (pinfunction "2_2") (pintype "passive"))
      (node (ref "U3") (pin "28") (pinfunction "P6.2_28") (pintype "bidirectional"))
    )
    (net (code "48") (name "TP_REF") (class "Default")
      (node (ref "R19") (pin "1") (pinfunction "1_1") (pintype "passive"))
      (node (ref "U3") (pin "29") (pinfunction "P6.5_29") (pintype "bidirectional"))
    )
    (net (code "49") (name "TXD") (class "Default")
      (node (ref "PAD3") (pin "1") (pinfunction "P_1") (pintype "passive"))
      (node (ref "U3") (pin "40") (pinfunction "P5.1_40") (pintype "bidirectional"))
    )
    (net (code "50") (name "VBAT") (class "Default")
      (node (ref "C2") (pin "1") (pinfunction "1_1") (pintype "passive"))
      (node (ref "C7") (pin "1") (pinfunction "1_1") (pintype "passive"))
      (node (ref "IC2") (pin "1") (pinfunction "IN_1") (pintype "bidirectional"))
      (node (ref "IC2") (pin "3") (pinfunction "EN_3") (pintype "bidirectional"))
      (node (ref "PAD1") (pin "1") (pinfunction "P_1") (pintype "passive"))
      (node (ref "R8") (pin "1") (pinfunction "1_1") (pintype "passive"))
      (node (ref "U2") (pin "3") (pinfunction "BAT_3") (pintype "bidirectional"))
      (node (ref "X5") (pin "1") (pinfunction "1_1") (pintype "passive"))
    )
    (net (code "51") (name "VBIAS_1") (class "Default")
      (node (ref "R17") (pin "2") (pinfunction "2_2") (pintype "passive"))
      (node (ref "U3") (pin "20") (pinfunction "P9.6_20") (pintype "bidirectional"))
    )
    (net (code "52") (name "VBIAS_2") (class "Default")
      (node (ref "R18") (pin "2") (pinfunction "2_2") (pintype "passive"))
      (node (ref "U3") (pin "19") (pinfunction "P9.5_19") (pintype "bidirectional"))
    )
    (net (code "53") (name "VBUS") (class "Default")
      (node (ref "C8") (pin "1") (pinfunction "1_1") (pintype "passive"))
      (node (ref "C9") (pin "1") (pinfunction "1_1") (pintype "passive"))
      (node (ref "LED1") (pin "A") (pinfunction "A_A") (pintype "passive"))
      (node (ref "MF") (pin "1") (pinfunction "1_1") (pintype "passive"))
      (node (ref "U2") (pin "4") (pinfunction "VCC_4") (pintype "power_in"))
    )
    (net (code "54") (name "VCC") (class "Default")
      (node (ref "C3") (pin "1") (pinfunction "1_1") (pintype "passive"))
      (node (ref "C5") (pin "1") (pinfunction "1_1") (pintype "passive"))
      (node (ref "C6") (pin "1") (pinfunction "1_1") (pintype "passive"))
      (node (ref "IC1") (pin "5") (pinfunction "OUT_5") (pintype "bidirectional"))
      (node (ref "R4") (pin "2") (pinfunction "2_2") (pintype "passive"))
      (node (ref "R5") (pin "2") (pinfunction "2_2") (pintype "passive"))
      (node (ref "R6") (pin "2") (pinfunction "2_2") (pintype "passive"))
      (node (ref "U1") (pin "6") (pinfunction "VDDIO_6") (pintype "power_in"))
      (node (ref "U1") (pin "8") (pinfunction "VDD_8") (pintype "power_in"))
      (node (ref "X2") (pin "1") (pinfunction "1_1") (pintype "passive"))
    )
    (net (code "55") (name "VDD") (class "Default")
      (node (ref "C12") (pin "1") (pinfunction "1_1") (pintype "passive"))
      (node (ref "C13") (pin "1") (pinfunction "1_1") (pintype "passive"))
      (node (ref "C15") (pin "1") (pinfunction "1_1") (pintype "passive"))
      (node (ref "C20") (pin "2") (pinfunction "2_2") (pintype "passive"))
      (node (ref "C4") (pin "1") (pinfunction "1_1") (pintype "passive"))
      (node (ref "IC2") (pin "5") (pinfunction "OUT_5") (pintype "bidirectional"))
      (node (ref "J5") (pin "4") (pinfunction "VDD_4") (pintype "bidirectional"))
      (node (ref "R13") (pin "1") (pinfunction "1_1") (pintype "passive"))
      (node (ref "R14") (pin "1") (pinfunction "1_1") (pintype "passive"))
      (node (ref "R20") (pin "1") (pinfunction "1_1") (pintype "passive"))
      (node (ref "U3") (pin "4") (pinfunction "VDD_4") (pintype "power_in"))
    )
    (net (code "56") (name "VS") (class "Default")
      (node (ref "C1") (pin "1") (pinfunction "1_1") (pintype "passive"))
      (node (ref "IC1") (pin "1") (pinfunction "IN_1") (pintype "bidirectional"))
      (node (ref "X3") (pin "1") (pinfunction "1_1") (pintype "passive"))
    )
    (net (code "57") (name "WCO_IN") (class "Default")
      (node (ref "C10") (pin "1") (pinfunction "1_1") (pintype "passive"))
      (node (ref "U3") (pin "5") (pinfunction "P0.0_5") (pintype "bidirectional"))
      (node (ref "Y1") (pin "1") (pinfunction "1_1") (pintype "passive"))
    )
    (net (code "58") (name "WCO_OUT") (class "Default")
      (node (ref "C11") (pin "1") (pinfunction "1_1") (pintype "passive"))
      (node (ref "U3") (pin "6") (pinfunction "P0.1_6") (pintype "bidirectional"))
      (node (ref "Y1") (pin "2") (pinfunction "2_2") (pintype "passive"))
    )
    (net (code "59") (name "_EN") (class "Default")
      (node (ref "U3") (pin "41") (pinfunction "P0.4_41") (pintype "bidirectional"))
      (node (ref "X6") (pin "1") (pinfunction "1_1") (pintype "passive"))
    )
    (net (code "60") (name "unconnected-(IC1-BYP-Pad4)") (class "Default")
      (node (ref "IC1") (pin "4") (pinfunction "BYP_4") (pintype "bidirectional"))
    )
    (net (code "61") (name "unconnected-(IC2-BYP-Pad4)") (class "Default")
      (node (ref "IC2") (pin "4") (pinfunction "BYP_4") (pintype "bidirectional"))
    )
    (net (code "62") (name "unconnected-(J2-ID-Pad4)") (class "Default")
      (node (ref "J2") (pin "4") (pinfunction "ID_4") (pintype "passive"))
    )
    (net (code "63") (name "unconnected-(J5-DAT1-Pad8)") (class "Default")
      (node (ref "J5") (pin "8") (pinfunction "DAT1_8") (pintype "bidirectional"))
    )
    (net (code "64") (name "unconnected-(J5-DAT2-Pad1)") (class "Default")
      (node (ref "J5") (pin "1") (pinfunction "DAT2_1") (pintype "bidirectional"))
    )
    (net (code "65") (name "unconnected-(R1-Pad2)") (class "Default")
      (node (ref "R1") (pin "2") (pinfunction "2_2") (pintype "passive"))
    )
    (net (code "66") (name "unconnected-(R2-Pad2)") (class "Default")
      (node (ref "R2") (pin "2") (pinfunction "2_2") (pintype "passive"))
    )
    (net (code "67") (name "unconnected-(R3-Pad2)") (class "Default")
      (node (ref "R3") (pin "2") (pinfunction "2_2") (pintype "passive"))
    )
    (net (code "68") (name "unconnected-(U3-P5.2-Pad38)") (class "Default")
      (node (ref "U3") (pin "38") (pinfunction "P5.2_38") (pintype "bidirectional"))
    )
    (net (code "69") (name "unconnected-(U3-P5.3-Pad37)") (class "Default")
      (node (ref "U3") (pin "37") (pinfunction "P5.3_37") (pintype "bidirectional"))
    )
    (net (code "70") (name "unconnected-(U3-P5.5-Pad36)") (class "Default")
      (node (ref "U3") (pin "36") (pinfunction "P5.5_36") (pintype "bidirectional"))
    )
    (net (code "71") (name "unconnected-(U3-P9.2-Pad21)") (class "Default")
      (node (ref "U3") (pin "21") (pinfunction "P9.2_21") (pintype "bidirectional"))
    )
    (net (code "72") (name "unconnected-(U3-P9.3-Pad9)") (class "Default")
      (node (ref "U3") (pin "9") (pinfunction "P9.3_9") (pintype "bidirectional"))
    )
    (net (code "73") (name "unconnected-(U3-P12.6-Pad34)") (class "Default")
      (node (ref "U3") (pin "34") (pinfunction "P12.6_34") (pintype "bidirectional"))
    )
    (net (code "74") (name "unconnected-(U3-P12.7-Pad35)") (class "Default")
      (node (ref "U3") (pin "35") (pinfunction "P12.7_35") (pintype "bidirectional"))
    )
  )
)
